# ECU_AutoRC_STEMP_r00.net
KiCad netlist of a schematic drawn in Altium Designer
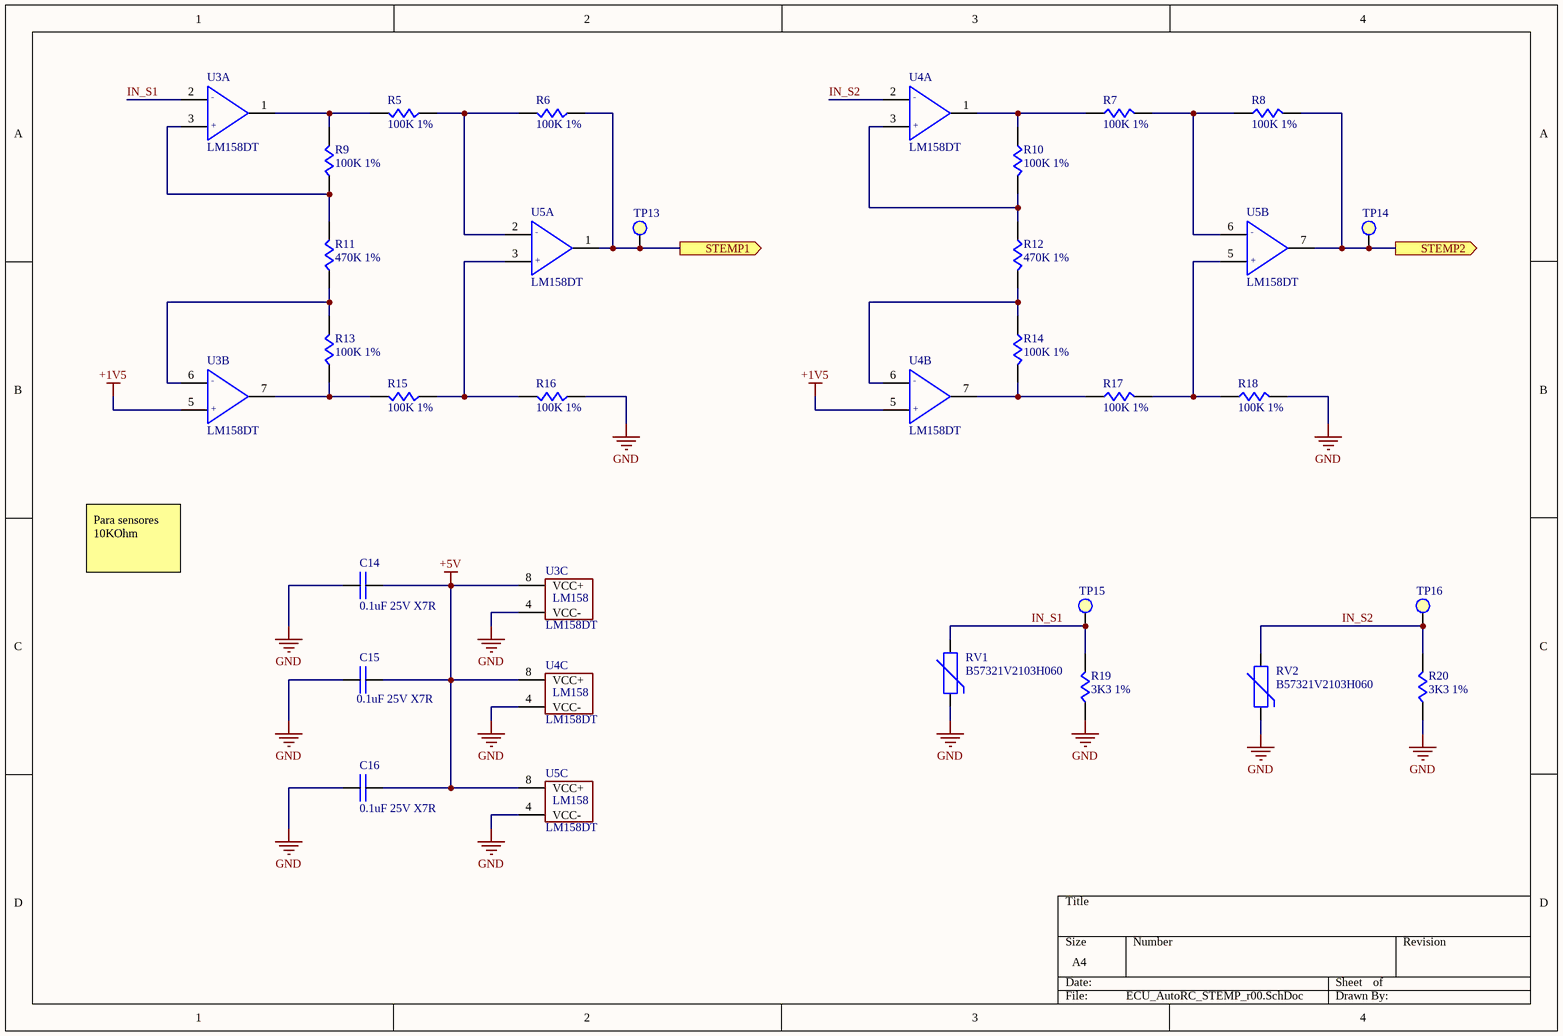
[diagram p0: ECU_AutoRC_STEMP_r00.SchDoc]

(export (version "E")
  (design (tool "Eeschema 10.0.6"))
  (components
    (comp (ref "C14")
      (value "0.1uF 25V X7R")
      (footprint "C_0805")
      (description "Non Polarizated Capacitor")
      (libsource (lib "ECU_AutoRC_r00") (part "Capacitor NP"))
    )
    (comp (ref "C15")
      (value "0.1uF 25V X7R")
      (footprint "C_0805")
      (description "Non Polarizated Capacitor")
      (libsource (lib "ECU_AutoRC_r00") (part "Capacitor NP"))
    )
    (comp (ref "C16")
      (value "0.1uF 25V X7R")
      (footprint "C_0805")
      (description "Non Polarizated Capacitor")
      (libsource (lib "ECU_AutoRC_r00") (part "Capacitor NP"))
    )
    (comp (ref "R5")
      (value "100K 1%")
      (footprint "R_0805")
      (description "Resistor")
      (libsource (lib "ECU_AutoRC_r00") (part "Resistor"))
    )
    (comp (ref "R6")
      (value "100K 1%")
      (footprint "R_0805")
      (description "Resistor")
      (libsource (lib "ECU_AutoRC_r00") (part "Resistor"))
    )
    (comp (ref "R7")
      (value "100K 1%")
      (footprint "R_0805")
      (description "Resistor")
      (libsource (lib "ECU_AutoRC_r00") (part "Resistor"))
    )
    (comp (ref "R8")
      (value "100K 1%")
      (footprint "R_0805")
      (description "Resistor")
      (libsource (lib "ECU_AutoRC_r00") (part "Resistor"))
    )
    (comp (ref "R9")
      (value "100K 1%")
      (footprint "R_0805")
      (description "Resistor")
      (libsource (lib "ECU_AutoRC_r00") (part "Resistor"))
    )
    (comp (ref "R10")
      (value "100K 1%")
      (footprint "R_0805")
      (description "Resistor")
      (libsource (lib "ECU_AutoRC_r00") (part "Resistor"))
    )
    (comp (ref "R11")
      (value "470K 1%")
      (footprint "R_0805")
      (description "Resistor")
      (libsource (lib "ECU_AutoRC_r00") (part "Resistor"))
    )
    (comp (ref "R12")
      (value "470K 1%")
      (footprint "R_0805")
      (description "Resistor")
      (libsource (lib "ECU_AutoRC_r00") (part "Resistor"))
    )
    (comp (ref "R13")
      (value "100K 1%")
      (footprint "R_0805")
      (description "Resistor")
      (libsource (lib "ECU_AutoRC_r00") (part "Resistor"))
    )
    (comp (ref "R14")
      (value "100K 1%")
      (footprint "R_0805")
      (description "Resistor")
      (libsource (lib "ECU_AutoRC_r00") (part "Resistor"))
    )
    (comp (ref "R15")
      (value "100K 1%")
      (footprint "R_0805")
      (description "Resistor")
      (libsource (lib "ECU_AutoRC_r00") (part "Resistor"))
    )
    (comp (ref "R16")
      (value "100K 1%")
      (footprint "R_0805")
      (description "Resistor")
      (libsource (lib "ECU_AutoRC_r00") (part "Resistor"))
    )
    (comp (ref "R17")
      (value "100K 1%")
      (footprint "R_0805")
      (description "Resistor")
      (libsource (lib "ECU_AutoRC_r00") (part "Resistor"))
    )
    (comp (ref "R18")
      (value "100K 1%")
      (footprint "R_0805")
      (description "Resistor")
      (libsource (lib "ECU_AutoRC_r00") (part "Resistor"))
    )
    (comp (ref "R19")
      (value "3K3 1%")
      (footprint "R_0805")
      (description "Resistor")
      (libsource (lib "ECU_AutoRC_r00") (part "Resistor"))
    )
    (comp (ref "R20")
      (value "3K3 1%")
      (footprint "R_0805")
      (description "Resistor")
      (libsource (lib "ECU_AutoRC_r00") (part "Resistor"))
    )
    (comp (ref "RV1")
      (value "B57321V2103H060")
      (footprint "R_0603")
      (description "Thermistor")
      (libsource (lib "ECU_AutoRC_r00") (part "Thermistor"))
    )
    (comp (ref "RV2")
      (value "B57321V2103H060")
      (footprint "R_0603")
      (description "Thermistor")
      (libsource (lib "ECU_AutoRC_r00") (part "Thermistor"))
    )
    (comp (ref "TP13")
      (value "Test Point")
      (footprint "TEST_POINT")
      (libsource (lib "ECU_AutoRC_r00") (part "TestPoint"))
    )
    (comp (ref "TP14")
      (value "Test Point")
      (footprint "TEST_POINT")
      (libsource (lib "ECU_AutoRC_r00") (part "TestPoint"))
    )
    (comp (ref "TP15")
      (value "Test Point")
      (footprint "TEST_POINT")
      (libsource (lib "ECU_AutoRC_r00") (part "TestPoint"))
    )
    (comp (ref "TP16")
      (value "Test Point")
      (footprint "TEST_POINT")
      (libsource (lib "ECU_AutoRC_r00") (part "TestPoint"))
    )
    (comp (ref "U3")
      (value "LM158DT")
      (footprint "IC_SO8")
      (description "Intrumentation Amplifier")
      (libsource (lib "ECU_AutoRC_r00") (part "LM158"))
    )
    (comp (ref "U4")
      (value "LM158DT")
      (footprint "IC_SO8")
      (description "Intrumentation Amplifier")
      (libsource (lib "ECU_AutoRC_r00") (part "LM158"))
    )
    (comp (ref "U5")
      (value "LM158DT")
      (footprint "IC_SO8")
      (description "Intrumentation Amplifier")
      (libsource (lib "ECU_AutoRC_r00") (part "LM158"))
    )
  )
  (nets
    (net (code "1") (name "+1V5") (class "Default")
      (node (ref "U3") (pin "5") (pinfunction "IN2+_5") (pintype "passive"))
      (node (ref "U4") (pin "5") (pinfunction "IN2+_5") (pintype "passive"))
    )
    (net (code "2") (name "+5V") (class "Default")
      (node (ref "C14") (pin "1") (pinfunction "1_1") (pintype "passive"))
      (node (ref "C15") (pin "1") (pinfunction "1_1") (pintype "passive"))
      (node (ref "C16") (pin "1") (pinfunction "1_1") (pintype "passive"))
      (node (ref "U3") (pin "8") (pinfunction "VCC+_8") (pintype "power_in"))
      (node (ref "U4") (pin "8") (pinfunction "VCC+_8") (pintype "power_in"))
      (node (ref "U5") (pin "8") (pinfunction "VCC+_8") (pintype "power_in"))
    )
    (net (code "3") (name "/IN_S1") (class "Default")
      (node (ref "R19") (pin "2") (pinfunction "2_2") (pintype "passive"))
      (node (ref "RV1") (pin "2") (pinfunction "2_2") (pintype "passive"))
      (node (ref "TP15") (pin "1") (pintype "passive"))
      (node (ref "U3") (pin "2") (pinfunction "IN1-_2") (pintype "passive"))
    )
    (net (code "4") (name "/IN_S2") (class "Default")
      (node (ref "R20") (pin "2") (pinfunction "2_2") (pintype "passive"))
      (node (ref "RV2") (pin "2") (pinfunction "2_2") (pintype "passive"))
      (node (ref "TP16") (pin "1") (pintype "passive"))
      (node (ref "U4") (pin "2") (pinfunction "IN1-_2") (pintype "passive"))
    )
    (net (code "5") (name "/STEMP1") (class "Default")
      (node (ref "R6") (pin "1") (pinfunction "1_1") (pintype "passive"))
      (node (ref "TP13") (pin "1") (pintype "passive"))
      (node (ref "U5") (pin "1") (pinfunction "OUT1_1") (pintype "passive"))
    )
    (net (code "6") (name "/STEMP2") (class "Default")
      (node (ref "R8") (pin "2") (pinfunction "2_2") (pintype "passive"))
      (node (ref "TP14") (pin "1") (pintype "passive"))
      (node (ref "U5") (pin "7") (pinfunction "OUT2_7") (pintype "passive"))
    )
    (net (code "7") (name "GND") (class "Default")
      (node (ref "C14") (pin "2") (pinfunction "2_2") (pintype "passive"))
      (node (ref "C15") (pin "2") (pinfunction "2_2") (pintype "passive"))
      (node (ref "C16") (pin "2") (pinfunction "2_2") (pintype "passive"))
      (node (ref "R16") (pin "1") (pinfunction "1_1") (pintype "passive"))
      (node (ref "R18") (pin "2") (pinfunction "2_2") (pintype "passive"))
      (node (ref "R19") (pin "1") (pinfunction "1_1") (pintype "passive"))
      (node (ref "R20") (pin "1") (pinfunction "1_1") (pintype "passive"))
      (node (ref "RV1") (pin "1") (pinfunction "1_1") (pintype "passive"))
      (node (ref "RV2") (pin "1") (pinfunction "1_1") (pintype "passive"))
      (node (ref "U3") (pin "4") (pinfunction "VCC-_4") (pintype "power_in"))
      (node (ref "U4") (pin "4") (pinfunction "VCC-_4") (pintype "power_in"))
      (node (ref "U5") (pin "4") (pinfunction "VCC-_4") (pintype "power_in"))
    )
    (net (code "8") (name "Net-(U3A-IN1+)") (class "Default")
      (node (ref "R11") (pin "2") (pinfunction "2_2") (pintype "passive"))
      (node (ref "R9") (pin "1") (pinfunction "1_1") (pintype "passive"))
      (node (ref "U3") (pin "3") (pinfunction "IN1+_3") (pintype "passive"))
    )
    (net (code "9") (name "Net-(U3A-OUT1)") (class "Default")
      (node (ref "R5") (pin "2") (pinfunction "2_2") (pintype "passive"))
      (node (ref "R9") (pin "2") (pinfunction "2_2") (pintype "passive"))
      (node (ref "U3") (pin "1") (pinfunction "OUT1_1") (pintype "passive"))
    )
    (net (code "10") (name "Net-(U3B-IN2-)") (class "Default")
      (node (ref "R11") (pin "1") (pinfunction "1_1") (pintype "passive"))
      (node (ref "R13") (pin "2") (pinfunction "2_2") (pintype "passive"))
      (node (ref "U3") (pin "6") (pinfunction "IN2-_6") (pintype "passive"))
    )
    (net (code "11") (name "Net-(U3B-OUT2)") (class "Default")
      (node (ref "R13") (pin "1") (pinfunction "1_1") (pintype "passive"))
      (node (ref "R15") (pin "2") (pinfunction "2_2") (pintype "passive"))
      (node (ref "U3") (pin "7") (pinfunction "OUT2_7") (pintype "passive"))
    )
    (net (code "12") (name "Net-(U4A-IN1+)") (class "Default")
      (node (ref "R10") (pin "2") (pinfunction "2_2") (pintype "passive"))
      (node (ref "R12") (pin "1") (pinfunction "1_1") (pintype "passive"))
      (node (ref "U4") (pin "3") (pinfunction "IN1+_3") (pintype "passive"))
    )
    (net (code "13") (name "Net-(U4A-OUT1)") (class "Default")
      (node (ref "R10") (pin "1") (pinfunction "1_1") (pintype "passive"))
      (node (ref "R7") (pin "1") (pinfunction "1_1") (pintype "passive"))
      (node (ref "U4") (pin "1") (pinfunction "OUT1_1") (pintype "passive"))
    )
    (net (code "14") (name "Net-(U4B-IN2-)") (class "Default")
      (node (ref "R12") (pin "2") (pinfunction "2_2") (pintype "passive"))
      (node (ref "R14") (pin "1") (pinfunction "1_1") (pintype "passive"))
      (node (ref "U4") (pin "6") (pinfunction "IN2-_6") (pintype "passive"))
    )
    (net (code "15") (name "Net-(U4B-OUT2)") (class "Default")
      (node (ref "R14") (pin "2") (pinfunction "2_2") (pintype "passive"))
      (node (ref "R17") (pin "1") (pinfunction "1_1") (pintype "passive"))
      (node (ref "U4") (pin "7") (pinfunction "OUT2_7") (pintype "passive"))
    )
    (net (code "16") (name "Net-(U5A-IN1+)") (class "Default")
      (node (ref "R15") (pin "1") (pinfunction "1_1") (pintype "passive"))
      (node (ref "R16") (pin "2") (pinfunction "2_2") (pintype "passive"))
      (node (ref "U5") (pin "3") (pinfunction "IN1+_3") (pintype "passive"))
    )
    (net (code "17") (name "Net-(U5A-IN1-)") (class "Default")
      (node (ref "R5") (pin "1") (pinfunction "1_1") (pintype "passive"))
      (node (ref "R6") (pin "2") (pinfunction "2_2") (pintype "passive"))
      (node (ref "U5") (pin "2") (pinfunction "IN1-_2") (pintype "passive"))
    )
    (net (code "18") (name "Net-(U5B-IN2+)") (class "Default")
      (node (ref "R17") (pin "2") (pinfunction "2_2") (pintype "passive"))
      (node (ref "R18") (pin "1") (pinfunction "1_1") (pintype "passive"))
      (node (ref "U5") (pin "5") (pinfunction "IN2+_5") (pintype "passive"))
    )
    (net (code "19") (name "Net-(U5B-IN2-)") (class "Default")
      (node (ref "R7") (pin "2") (pinfunction "2_2") (pintype "passive"))
      (node (ref "R8") (pin "1") (pinfunction "1_1") (pintype "passive"))
      (node (ref "U5") (pin "6") (pinfunction "IN2-_6") (pintype "passive"))
    )
  )
)
